# placaPadr_oATmega328.net
KiCad netlist of a schematic drawn in EAGLE
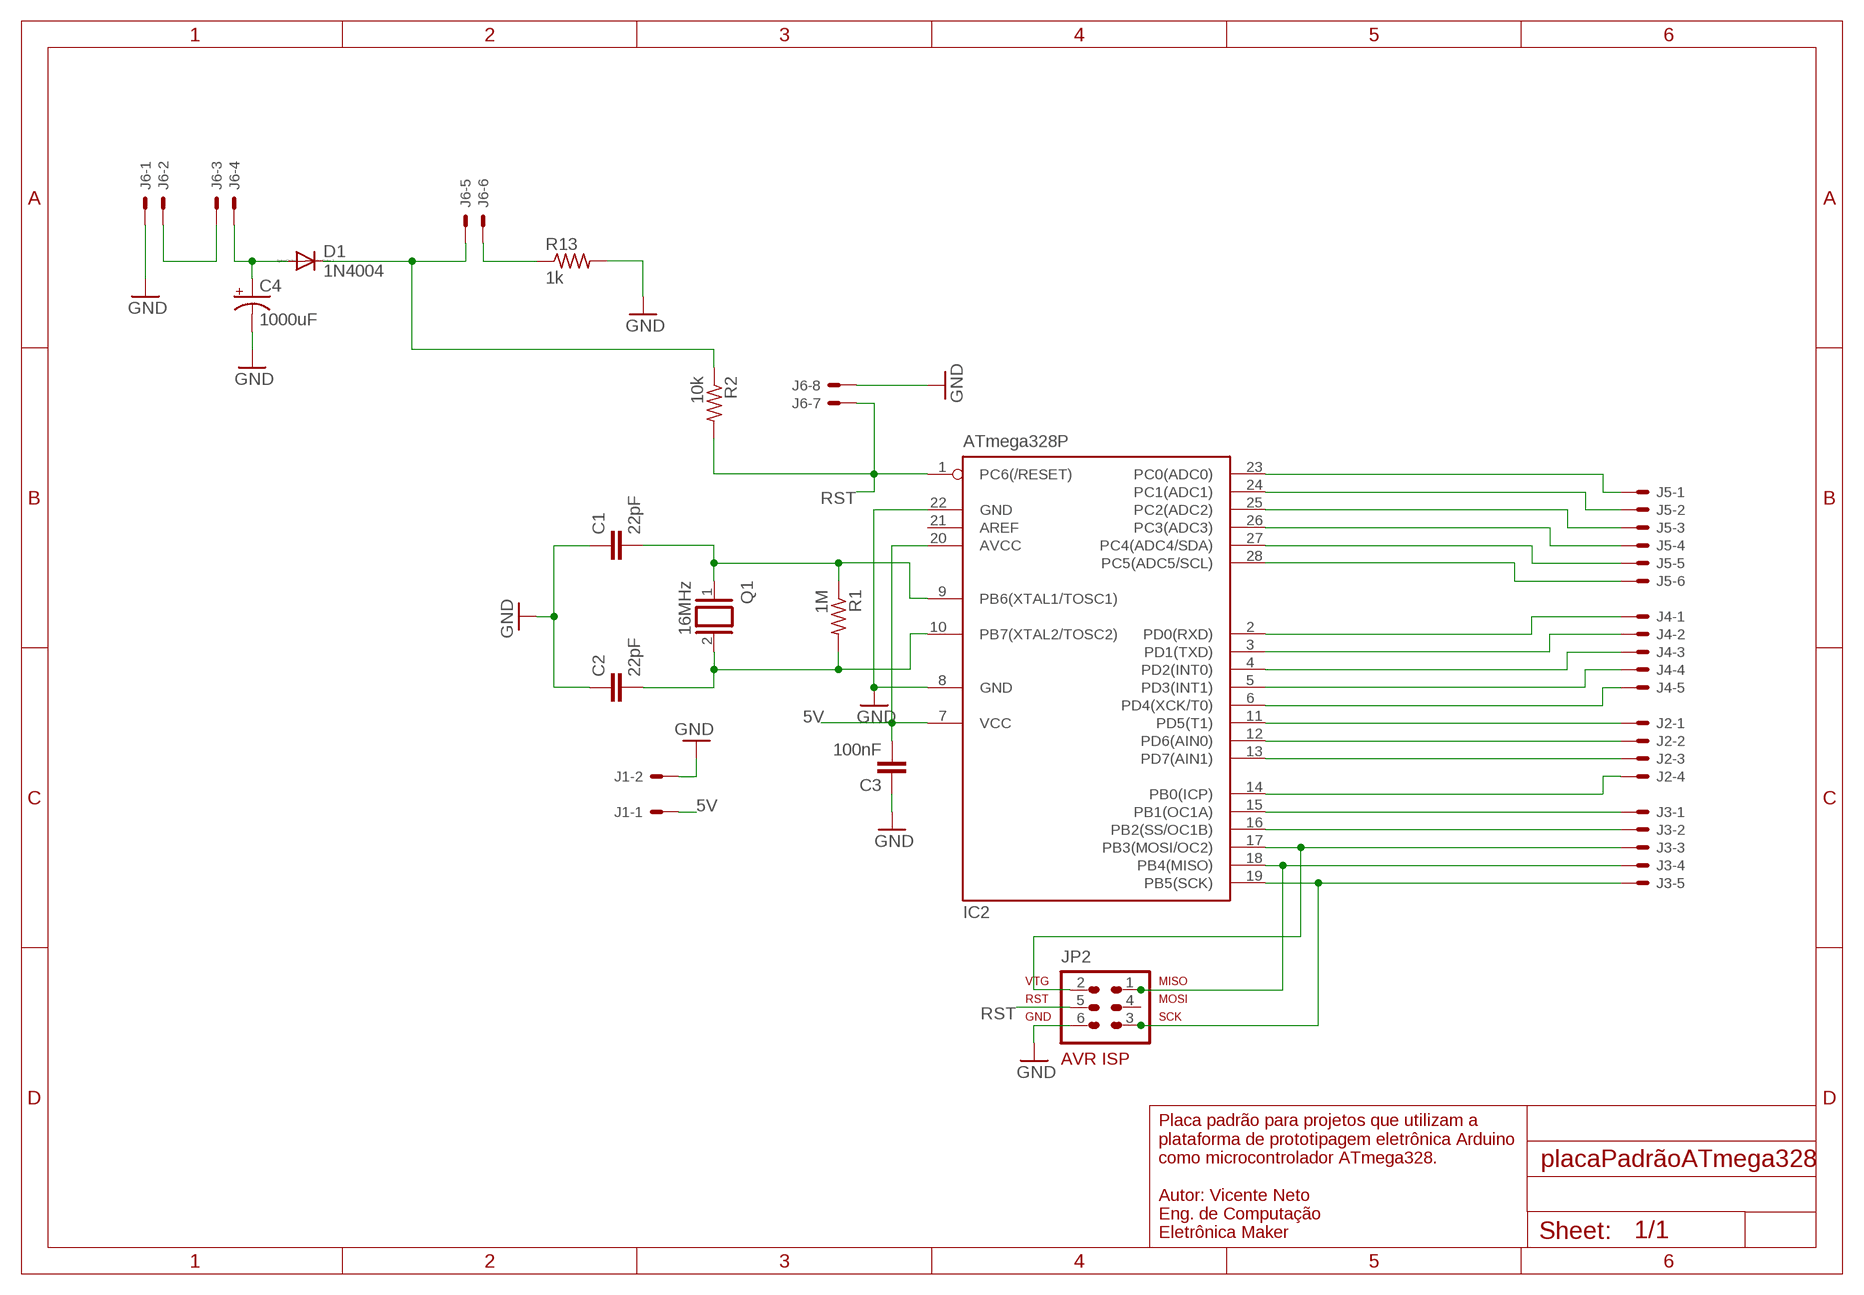
[diagram p0: schematic, sheet 1]

(export (version "E")
  (design (tool "Eeschema 10.0.6"))
  (components
    (comp (ref "C1")
      (value "22pF")
      (footprint "eagle-import:C025-025X050")
      (libsource (lib "eagle-import") (part "C-EU025-025X050"))
    )
    (comp (ref "C2")
      (value "22pF")
      (footprint "eagle-import:C025-025X050")
      (libsource (lib "eagle-import") (part "C-EU025-025X050"))
    )
    (comp (ref "C3")
      (value "100nF")
      (footprint "eagle-import:C025-025X050")
      (libsource (lib "eagle-import") (part "C-EU025-025X050"))
    )
    (comp (ref "C4")
      (value "1000uF")
      (footprint "eagle-import:E5-10,5")
      (libsource (lib "eagle-import") (part "CPOL-USE5-10.5"))
    )
    (comp (ref "D1")
      (value "1N4004")
      (footprint "eagle-import:DO41-10")
      (libsource (lib "eagle-import") (part "1N4004"))
    )
    (comp (ref "IC2")
      (value "ATmega328P")
      (footprint "eagle-import:DIL28-3")
      (libsource (lib "eagle-import") (part "MEGA8-P"))
    )
    (comp (ref "J1")
      (value "22-27-2021-02")
      (footprint "eagle-import:6410-02")
      (libsource (lib "eagle-import") (part "22-?-0227-2021"))
    )
    (comp (ref "J2")
      (value "22-27-2041-04")
      (footprint "eagle-import:6410-04")
      (libsource (lib "eagle-import") (part "22-?-0427-2041"))
    )
    (comp (ref "J3")
      (value "22-27-2051-05")
      (footprint "eagle-import:6410-05")
      (libsource (lib "eagle-import") (part "22-?-0527-2051"))
    )
    (comp (ref "J4")
      (value "22-27-2051-05")
      (footprint "eagle-import:6410-05")
      (libsource (lib "eagle-import") (part "22-?-0527-2051"))
    )
    (comp (ref "J5")
      (value "22-27-2061-06")
      (footprint "eagle-import:6410-06")
      (libsource (lib "eagle-import") (part "22-?-0627-2061"))
    )
    (comp (ref "J6")
      (value "22-27-2081-08")
      (footprint "eagle-import:6410-08")
      (libsource (lib "eagle-import") (part "22-?-0827-2081"))
    )
    (comp (ref "JP2")
      (value "ICSP")
      (footprint "eagle-import:AVR-ISP-6")
      (libsource (lib "eagle-import") (part "AVR-ISP-6"))
    )
    (comp (ref "Q1")
      (value "16MHz")
      (footprint "eagle-import:QS")
      (libsource (lib "eagle-import") (part "XTAL/S"))
    )
    (comp (ref "R1")
      (value "1M")
      (footprint "eagle-import:0204_7")
      (libsource (lib "eagle-import") (part "R-US_0204/7"))
    )
    (comp (ref "R2")
      (value "10k")
      (footprint "eagle-import:0204_7")
      (libsource (lib "eagle-import") (part "R-US_0204/7"))
    )
    (comp (ref "R13")
      (value "1k")
      (footprint "eagle-import:0204_7")
      (libsource (lib "eagle-import") (part "R-US_0204/7"))
    )
  )
  (nets
    (net (code "1") (name "/5V") (class "Default")
      (node (ref "C3") (pin "2") (pinfunction "2_2") (pintype "passive"))
      (node (ref "D1") (pin "C") (pinfunction "C_C") (pintype "passive"))
      (node (ref "IC2") (pin "20") (pinfunction "AVCC_20") (pintype "power_in"))
      (node (ref "IC2") (pin "7") (pinfunction "VCC_7") (pintype "power_in"))
      (node (ref "J1") (pin "1") (pinfunction "S_1") (pintype "passive"))
      (node (ref "J6") (pin "5") (pinfunction "S_5") (pintype "passive"))
      (node (ref "R2") (pin "1") (pinfunction "1_1") (pintype "passive"))
    )
    (net (code "2") (name "/RST") (class "Default")
      (node (ref "IC2") (pin "1") (pinfunction "PC6(/RESET)_1") (pintype "bidirectional"))
      (node (ref "J6") (pin "7") (pinfunction "S_7") (pintype "passive"))
      (node (ref "JP2") (pin "5") (pinfunction "5_5") (pintype "passive"))
      (node (ref "R2") (pin "2") (pinfunction "2_2") (pintype "passive"))
    )
    (net (code "3") (name "GND") (class "Default")
      (node (ref "C1") (pin "1") (pinfunction "1_1") (pintype "passive"))
      (node (ref "C2") (pin "1") (pinfunction "1_1") (pintype "passive"))
      (node (ref "C3") (pin "1") (pinfunction "1_1") (pintype "passive"))
      (node (ref "C4") (pin "-") (pinfunction "-_-") (pintype "passive"))
      (node (ref "IC2") (pin "22") (pinfunction "GND_22") (pintype "power_in"))
      (node (ref "IC2") (pin "8") (pinfunction "GND_8") (pintype "power_in"))
      (node (ref "J1") (pin "2") (pinfunction "S_2") (pintype "passive"))
      (node (ref "J6") (pin "1") (pinfunction "S_1") (pintype "passive"))
      (node (ref "J6") (pin "8") (pinfunction "S_8") (pintype "passive"))
      (node (ref "JP2") (pin "6") (pinfunction "6_6") (pintype "passive"))
      (node (ref "R13") (pin "2") (pinfunction "2_2") (pintype "passive"))
    )
    (net (code "4") (name "Net-(IC2-PB0(ICP))") (class "Default")
      (node (ref "IC2") (pin "14") (pinfunction "PB0(ICP)_14") (pintype "bidirectional"))
      (node (ref "J2") (pin "4") (pinfunction "S_4") (pintype "passive"))
    )
    (net (code "5") (name "Net-(IC2-PB1(OC1A))") (class "Default")
      (node (ref "IC2") (pin "15") (pinfunction "PB1(OC1A)_15") (pintype "bidirectional"))
      (node (ref "J3") (pin "1") (pinfunction "S_1") (pintype "passive"))
    )
    (net (code "6") (name "Net-(IC2-PB2(SS{slash}OC1B))") (class "Default")
      (node (ref "IC2") (pin "16") (pinfunction "PB2(SS/OC1B)_16") (pintype "bidirectional"))
      (node (ref "J3") (pin "2") (pinfunction "S_2") (pintype "passive"))
    )
    (net (code "7") (name "Net-(IC2-PB3(MOSI{slash}OC2))") (class "Default")
      (node (ref "IC2") (pin "17") (pinfunction "PB3(MOSI/OC2)_17") (pintype "bidirectional"))
      (node (ref "J3") (pin "3") (pinfunction "S_3") (pintype "passive"))
      (node (ref "JP2") (pin "2") (pinfunction "2_2") (pintype "passive"))
    )
    (net (code "8") (name "Net-(IC2-PB4(MISO))") (class "Default")
      (node (ref "IC2") (pin "18") (pinfunction "PB4(MISO)_18") (pintype "bidirectional"))
      (node (ref "J3") (pin "4") (pinfunction "S_4") (pintype "passive"))
      (node (ref "JP2") (pin "1") (pinfunction "1_1") (pintype "passive"))
    )
    (net (code "9") (name "Net-(IC2-PB5(SCK))") (class "Default")
      (node (ref "IC2") (pin "19") (pinfunction "PB5(SCK)_19") (pintype "bidirectional"))
      (node (ref "J3") (pin "5") (pinfunction "S_5") (pintype "passive"))
      (node (ref "JP2") (pin "3") (pinfunction "3_3") (pintype "passive"))
    )
    (net (code "10") (name "Net-(IC2-PB6(XTAL1{slash}TOSC1))") (class "Default")
      (node (ref "C1") (pin "2") (pinfunction "2_2") (pintype "passive"))
      (node (ref "IC2") (pin "9") (pinfunction "PB6(XTAL1/TOSC1)_9") (pintype "bidirectional"))
      (node (ref "Q1") (pin "1") (pinfunction "1_1") (pintype "passive"))
      (node (ref "R1") (pin "1") (pinfunction "1_1") (pintype "passive"))
    )
    (net (code "11") (name "Net-(IC2-PB7(XTAL2{slash}TOSC2))") (class "Default")
      (node (ref "C2") (pin "2") (pinfunction "2_2") (pintype "passive"))
      (node (ref "IC2") (pin "10") (pinfunction "PB7(XTAL2/TOSC2)_10") (pintype "bidirectional"))
      (node (ref "Q1") (pin "2") (pinfunction "2_2") (pintype "passive"))
      (node (ref "R1") (pin "2") (pinfunction "2_2") (pintype "passive"))
    )
    (net (code "12") (name "Net-(IC2-PC0(ADC0))") (class "Default")
      (node (ref "IC2") (pin "23") (pinfunction "PC0(ADC0)_23") (pintype "bidirectional"))
      (node (ref "J5") (pin "1") (pinfunction "S_1") (pintype "passive"))
    )
    (net (code "13") (name "Net-(IC2-PC1(ADC1))") (class "Default")
      (node (ref "IC2") (pin "24") (pinfunction "PC1(ADC1)_24") (pintype "bidirectional"))
      (node (ref "J5") (pin "2") (pinfunction "S_2") (pintype "passive"))
    )
    (net (code "14") (name "Net-(IC2-PC2(ADC2))") (class "Default")
      (node (ref "IC2") (pin "25") (pinfunction "PC2(ADC2)_25") (pintype "bidirectional"))
      (node (ref "J5") (pin "3") (pinfunction "S_3") (pintype "passive"))
    )
    (net (code "15") (name "Net-(IC2-PC3(ADC3))") (class "Default")
      (node (ref "IC2") (pin "26") (pinfunction "PC3(ADC3)_26") (pintype "bidirectional"))
      (node (ref "J5") (pin "4") (pinfunction "S_4") (pintype "passive"))
    )
    (net (code "16") (name "Net-(IC2-PC4(ADC4{slash}SDA))") (class "Default")
      (node (ref "IC2") (pin "27") (pinfunction "PC4(ADC4/SDA)_27") (pintype "bidirectional"))
      (node (ref "J5") (pin "5") (pinfunction "S_5") (pintype "passive"))
    )
    (net (code "17") (name "Net-(IC2-PC5(ADC5{slash}SCL))") (class "Default")
      (node (ref "IC2") (pin "28") (pinfunction "PC5(ADC5/SCL)_28") (pintype "bidirectional"))
      (node (ref "J5") (pin "6") (pinfunction "S_6") (pintype "passive"))
    )
    (net (code "18") (name "Net-(IC2-PD0(RXD))") (class "Default")
      (node (ref "IC2") (pin "2") (pinfunction "PD0(RXD)_2") (pintype "bidirectional"))
      (node (ref "J4") (pin "1") (pinfunction "S_1") (pintype "passive"))
    )
    (net (code "19") (name "Net-(IC2-PD1(TXD))") (class "Default")
      (node (ref "IC2") (pin "3") (pinfunction "PD1(TXD)_3") (pintype "bidirectional"))
      (node (ref "J4") (pin "2") (pinfunction "S_2") (pintype "passive"))
    )
    (net (code "20") (name "Net-(IC2-PD2(INT0))") (class "Default")
      (node (ref "IC2") (pin "4") (pinfunction "PD2(INT0)_4") (pintype "bidirectional"))
      (node (ref "J4") (pin "3") (pinfunction "S_3") (pintype "passive"))
    )
    (net (code "21") (name "Net-(IC2-PD3(INT1))") (class "Default")
      (node (ref "IC2") (pin "5") (pinfunction "PD3(INT1)_5") (pintype "bidirectional"))
      (node (ref "J4") (pin "4") (pinfunction "S_4") (pintype "passive"))
    )
    (net (code "22") (name "Net-(IC2-PD4(XCK{slash}T0))") (class "Default")
      (node (ref "IC2") (pin "6") (pinfunction "PD4(XCK/T0)_6") (pintype "bidirectional"))
      (node (ref "J4") (pin "5") (pinfunction "S_5") (pintype "passive"))
    )
    (net (code "23") (name "Net-(IC2-PD5(T1))") (class "Default")
      (node (ref "IC2") (pin "11") (pinfunction "PD5(T1)_11") (pintype "bidirectional"))
      (node (ref "J2") (pin "1") (pinfunction "S_1") (pintype "passive"))
    )
    (net (code "24") (name "Net-(IC2-PD6(AIN0))") (class "Default")
      (node (ref "IC2") (pin "12") (pinfunction "PD6(AIN0)_12") (pintype "bidirectional"))
      (node (ref "J2") (pin "2") (pinfunction "S_2") (pintype "passive"))
    )
    (net (code "25") (name "Net-(IC2-PD7(AIN1))") (class "Default")
      (node (ref "IC2") (pin "13") (pinfunction "PD7(AIN1)_13") (pintype "bidirectional"))
      (node (ref "J2") (pin "3") (pinfunction "S_3") (pintype "passive"))
    )
    (net (code "26") (name "Net-(J6B-S)") (class "Default")
      (node (ref "J6") (pin "2") (pinfunction "S_2") (pintype "passive"))
      (node (ref "J6") (pin "3") (pinfunction "S_3") (pintype "passive"))
    )
    (net (code "27") (name "Net-(J6D-S)") (class "Default")
      (node (ref "C4") (pin "+") (pinfunction "+_+") (pintype "passive"))
      (node (ref "D1") (pin "A") (pinfunction "A_A") (pintype "passive"))
      (node (ref "J6") (pin "4") (pinfunction "S_4") (pintype "passive"))
    )
    (net (code "28") (name "Net-(J6F-S)") (class "Default")
      (node (ref "J6") (pin "6") (pinfunction "S_6") (pintype "passive"))
      (node (ref "R13") (pin "1") (pinfunction "1_1") (pintype "passive"))
    )
    (net (code "29") (name "unconnected-(IC2-AREF-Pad21)") (class "Default")
      (node (ref "IC2") (pin "21") (pinfunction "AREF_21") (pintype "passive"))
    )
    (net (code "30") (name "unconnected-(JP2-Pad4)") (class "Default")
      (node (ref "JP2") (pin "4") (pinfunction "4_4") (pintype "passive"))
    )
  )
)
